# TouchPanelPrototype.net
KiCad netlist of a schematic drawn in EAGLE
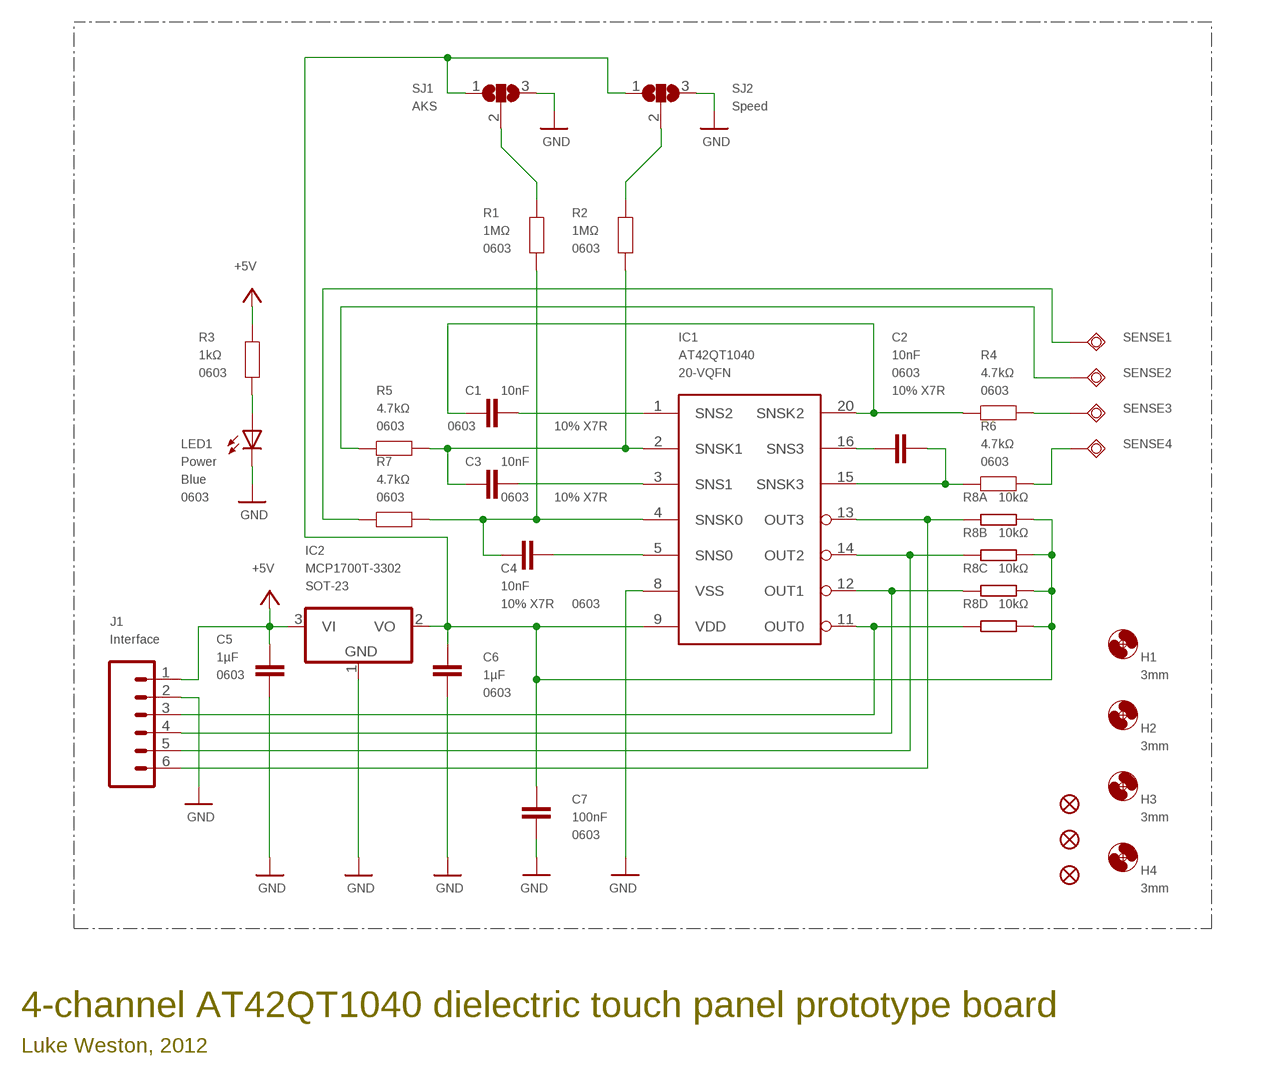
[diagram p0: schematic, sheet 1, part 1 of 2]
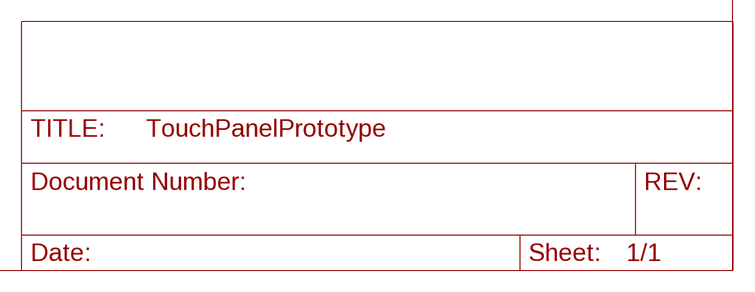
[diagram p1: schematic, sheet 1, part 2 of 2]

(export (version "E")
  (design (tool "Eeschema 10.0.6"))
  (components
    (comp (ref "C1")
      (value "10nF")
      (footprint "eagle-import:0603")
      (fields (field (name "INFO") "10% X7R") (field (name "PACKAGE") "0603"))
      (libsource (lib "eagle-import") (part "CAP0603"))
    )
    (comp (ref "C2")
      (value "10nF")
      (footprint "eagle-import:0603")
      (fields (field (name "INFO") "10% X7R") (field (name "PACKAGE") "0603"))
      (libsource (lib "eagle-import") (part "CAP0603"))
    )
    (comp (ref "C3")
      (value "10nF")
      (footprint "eagle-import:0603")
      (fields (field (name "INFO") "10% X7R") (field (name "PACKAGE") "0603"))
      (libsource (lib "eagle-import") (part "CAP0603"))
    )
    (comp (ref "C4")
      (value "10nF")
      (footprint "eagle-import:0603")
      (fields (field (name "INFO") "10% X7R") (field (name "PACKAGE") "0603"))
      (libsource (lib "eagle-import") (part "CAP0603"))
    )
    (comp (ref "C5")
      (value "1µF")
      (footprint "eagle-import:0603")
      (fields (field (name "PACKAGE") "0603"))
      (libsource (lib "eagle-import") (part "CAP0603"))
    )
    (comp (ref "C6")
      (value "1µF")
      (footprint "eagle-import:0603")
      (fields (field (name "PACKAGE") "0603"))
      (libsource (lib "eagle-import") (part "CAP0603"))
    )
    (comp (ref "C7")
      (value "100nF")
      (footprint "eagle-import:0603")
      (fields (field (name "PACKAGE") "0603"))
      (libsource (lib "eagle-import") (part "CAP0603"))
    )
    (comp (ref "H1")
      (value "3mm")
      (footprint "eagle-import:3,0")
      (libsource (lib "eagle-import") (part "MOUNT-HOLE3.0"))
    )
    (comp (ref "H2")
      (value "3mm")
      (footprint "eagle-import:3,0")
      (libsource (lib "eagle-import") (part "MOUNT-HOLE3.0"))
    )
    (comp (ref "H3")
      (value "3mm")
      (footprint "eagle-import:3,0")
      (libsource (lib "eagle-import") (part "MOUNT-HOLE3.0"))
    )
    (comp (ref "H4")
      (value "3mm")
      (footprint "eagle-import:3,0")
      (libsource (lib "eagle-import") (part "MOUNT-HOLE3.0"))
    )
    (comp (ref "IC1")
      (value "AT42QT1040")
      (footprint "eagle-import:QFN_MLF20")
      (fields (field (name "PACKAGE") "20-VQFN"))
      (libsource (lib "eagle-import") (part "AT42QT1040"))
    )
    (comp (ref "IC2")
      (value "MCP1700T-3302")
      (footprint "eagle-import:SOT23")
      (fields (field (name "PACKAGE") "SOT-23"))
      (libsource (lib "eagle-import") (part "MCP1703CB"))
    )
    (comp (ref "J1")
      (value "Interface")
      (footprint "eagle-import:1X06")
      (libsource (lib "eagle-import") (part "M06SIP"))
    )
    (comp (ref "JP1")
      (value "FIDUCIAL1X2")
      (footprint "eagle-import:FIDUCIAL-1X2")
      (libsource (lib "eagle-import") (part "FIDUCIAL1X2"))
    )
    (comp (ref "JP2")
      (value "FIDUCIAL1X2")
      (footprint "eagle-import:FIDUCIAL-1X2")
      (libsource (lib "eagle-import") (part "FIDUCIAL1X2"))
    )
    (comp (ref "JP3")
      (value "FIDUCIAL1X2")
      (footprint "eagle-import:FIDUCIAL-1X2")
      (libsource (lib "eagle-import") (part "FIDUCIAL1X2"))
    )
    (comp (ref "LED1")
      (value "Power")
      (footprint "eagle-import:LED-0603")
      (fields (field (name "COLOUR") "Blue") (field (name "PACKAGE") "0603"))
      (libsource (lib "eagle-import") (part "LED0603"))
    )
    (comp (ref "R1")
      (value "1MΩ")
      (footprint "eagle-import:0603")
      (fields (field (name "PACKAGE") "0603"))
      (libsource (lib "eagle-import") (part "RESISTOR0603"))
    )
    (comp (ref "R2")
      (value "1MΩ")
      (footprint "eagle-import:0603")
      (fields (field (name "PACKAGE") "0603"))
      (libsource (lib "eagle-import") (part "RESISTOR0603"))
    )
    (comp (ref "R3")
      (value "1kΩ")
      (footprint "eagle-import:0603")
      (fields (field (name "PACKAGE") "0603"))
      (libsource (lib "eagle-import") (part "RESISTOR0603"))
    )
    (comp (ref "R4")
      (value "4.7kΩ")
      (footprint "eagle-import:0603")
      (fields (field (name "PACKAGE") "0603"))
      (libsource (lib "eagle-import") (part "RESISTOR0603"))
    )
    (comp (ref "R5")
      (value "4.7kΩ")
      (footprint "eagle-import:0603")
      (fields (field (name "PACKAGE") "0603"))
      (libsource (lib "eagle-import") (part "RESISTOR0603"))
    )
    (comp (ref "R6")
      (value "4.7kΩ")
      (footprint "eagle-import:0603")
      (fields (field (name "PACKAGE") "0603"))
      (libsource (lib "eagle-import") (part "RESISTOR0603"))
    )
    (comp (ref "R7")
      (value "4.7kΩ")
      (footprint "eagle-import:0603")
      (fields (field (name "PACKAGE") "0603"))
      (libsource (lib "eagle-import") (part "RESISTOR0603"))
    )
    (comp (ref "R8")
      (value "10kΩ")
      (footprint "eagle-import:CAY16")
      (libsource (lib "eagle-import") (part "CAY16"))
    )
    (comp (ref "SENSE1")
      (value "TPSQTP20R")
      (footprint "eagle-import:TP20R")
      (libsource (lib "eagle-import") (part "TPSQTP20R"))
    )
    (comp (ref "SENSE2")
      (value "TPSQTP20R")
      (footprint "eagle-import:TP20R")
      (libsource (lib "eagle-import") (part "TPSQTP20R"))
    )
    (comp (ref "SENSE3")
      (value "TPSQTP20R")
      (footprint "eagle-import:TP20R")
      (libsource (lib "eagle-import") (part "TPSQTP20R"))
    )
    (comp (ref "SENSE4")
      (value "TPSQTP20R")
      (footprint "eagle-import:TP20R")
      (libsource (lib "eagle-import") (part "TPSQTP20R"))
    )
    (comp (ref "SJ1")
      (value "AKS")
      (footprint "eagle-import:SJ_2")
      (libsource (lib "eagle-import") (part "SJ2W"))
    )
    (comp (ref "SJ2")
      (value "Speed")
      (footprint "eagle-import:SJ_2")
      (libsource (lib "eagle-import") (part "SJ2W"))
    )
  )
  (nets
    (net (code "1") (name "+5V") (class "Default")
      (node (ref "C5") (pin "2") (pinfunction "2_2") (pintype "passive"))
      (node (ref "IC2") (pin "3") (pinfunction "VI_3") (pintype "input"))
      (node (ref "J1") (pin "1") (pinfunction "1_1") (pintype "passive"))
      (node (ref "R3") (pin "1") (pinfunction "1_1") (pintype "passive"))
    )
    (net (code "2") (name "GND") (class "Default")
      (node (ref "C5") (pin "1") (pinfunction "1_1") (pintype "passive"))
      (node (ref "C6") (pin "1") (pinfunction "1_1") (pintype "passive"))
      (node (ref "C7") (pin "1") (pinfunction "1_1") (pintype "passive"))
      (node (ref "IC1") (pin "8") (pinfunction "VSS_8") (pintype "power_in"))
      (node (ref "IC2") (pin "1") (pinfunction "GND_1") (pintype "passive"))
      (node (ref "J1") (pin "2") (pinfunction "2_2") (pintype "passive"))
      (node (ref "LED1") (pin "C") (pinfunction "C_C") (pintype "passive"))
      (node (ref "SJ1") (pin "3") (pinfunction "3_3") (pintype "passive"))
      (node (ref "SJ2") (pin "3") (pinfunction "3_3") (pintype "passive"))
    )
    (net (code "3") (name "Net-(IC1-OUT0)") (class "Default")
      (node (ref "IC1") (pin "11") (pinfunction "OUT0_11") (pintype "output"))
      (node (ref "J1") (pin "3") (pinfunction "3_3") (pintype "passive"))
      (node (ref "R8") (pin "5") (pinfunction "2_5") (pintype "passive"))
    )
    (net (code "4") (name "Net-(IC1-OUT1)") (class "Default")
      (node (ref "IC1") (pin "12") (pinfunction "OUT1_12") (pintype "output"))
      (node (ref "J1") (pin "4") (pinfunction "4_4") (pintype "passive"))
      (node (ref "R8") (pin "6") (pinfunction "2_6") (pintype "passive"))
    )
    (net (code "5") (name "Net-(IC1-OUT2)") (class "Default")
      (node (ref "IC1") (pin "14") (pinfunction "OUT2_14") (pintype "output"))
      (node (ref "J1") (pin "5") (pinfunction "5_5") (pintype "passive"))
      (node (ref "R8") (pin "7") (pinfunction "2_7") (pintype "passive"))
    )
    (net (code "6") (name "Net-(IC1-OUT3)") (class "Default")
      (node (ref "IC1") (pin "13") (pinfunction "OUT3_13") (pintype "output"))
      (node (ref "J1") (pin "6") (pinfunction "6_6") (pintype "passive"))
      (node (ref "R8") (pin "8") (pinfunction "2_8") (pintype "passive"))
    )
    (net (code "7") (name "Net-(IC1-SNS0)") (class "Default")
      (node (ref "C4") (pin "1") (pinfunction "1_1") (pintype "passive"))
      (node (ref "IC1") (pin "5") (pinfunction "SNS0_5") (pintype "bidirectional"))
    )
    (net (code "8") (name "Net-(IC1-SNS1)") (class "Default")
      (node (ref "C3") (pin "1") (pinfunction "1_1") (pintype "passive"))
      (node (ref "IC1") (pin "3") (pinfunction "SNS1_3") (pintype "bidirectional"))
    )
    (net (code "9") (name "Net-(IC1-SNS2)") (class "Default")
      (node (ref "C1") (pin "1") (pinfunction "1_1") (pintype "passive"))
      (node (ref "IC1") (pin "1") (pinfunction "SNS2_1") (pintype "bidirectional"))
    )
    (net (code "10") (name "Net-(IC1-SNS3)") (class "Default")
      (node (ref "C2") (pin "2") (pinfunction "2_2") (pintype "passive"))
      (node (ref "IC1") (pin "16") (pinfunction "SNS3_16") (pintype "bidirectional"))
    )
    (net (code "11") (name "Net-(IC1-SNSK0)") (class "Default")
      (node (ref "C4") (pin "2") (pinfunction "2_2") (pintype "passive"))
      (node (ref "IC1") (pin "4") (pinfunction "SNSK0_4") (pintype "bidirectional"))
      (node (ref "R1") (pin "2") (pinfunction "2_2") (pintype "passive"))
      (node (ref "R7") (pin "1") (pinfunction "1_1") (pintype "passive"))
    )
    (net (code "12") (name "Net-(IC1-SNSK1)") (class "Default")
      (node (ref "C3") (pin "2") (pinfunction "2_2") (pintype "passive"))
      (node (ref "IC1") (pin "2") (pinfunction "SNSK1_2") (pintype "bidirectional"))
      (node (ref "R2") (pin "2") (pinfunction "2_2") (pintype "passive"))
      (node (ref "R5") (pin "1") (pinfunction "1_1") (pintype "passive"))
    )
    (net (code "13") (name "Net-(IC1-SNSK2)") (class "Default")
      (node (ref "C1") (pin "2") (pinfunction "2_2") (pintype "passive"))
      (node (ref "IC1") (pin "20") (pinfunction "SNSK2_20") (pintype "bidirectional"))
      (node (ref "R4") (pin "2") (pinfunction "2_2") (pintype "passive"))
    )
    (net (code "14") (name "Net-(IC1-SNSK3)") (class "Default")
      (node (ref "C2") (pin "1") (pinfunction "1_1") (pintype "passive"))
      (node (ref "IC1") (pin "15") (pinfunction "SNSK3_15") (pintype "bidirectional"))
      (node (ref "R6") (pin "2") (pinfunction "2_2") (pintype "passive"))
    )
    (net (code "15") (name "Net-(IC1-VDD)") (class "Default")
      (node (ref "C6") (pin "2") (pinfunction "2_2") (pintype "passive"))
      (node (ref "C7") (pin "2") (pinfunction "2_2") (pintype "passive"))
      (node (ref "IC1") (pin "9") (pinfunction "VDD_9") (pintype "power_in"))
      (node (ref "IC2") (pin "2") (pinfunction "VO_2") (pintype "passive"))
      (node (ref "R8") (pin "1") (pinfunction "1_1") (pintype "passive"))
      (node (ref "R8") (pin "2") (pinfunction "1_2") (pintype "passive"))
      (node (ref "R8") (pin "3") (pinfunction "1_3") (pintype "passive"))
      (node (ref "R8") (pin "4") (pinfunction "1_4") (pintype "passive"))
      (node (ref "SJ1") (pin "1") (pinfunction "1_1") (pintype "passive"))
      (node (ref "SJ2") (pin "1") (pinfunction "1_1") (pintype "passive"))
    )
    (net (code "16") (name "Net-(LED1-PadA)") (class "Default")
      (node (ref "LED1") (pin "A") (pinfunction "A_A") (pintype "passive"))
      (node (ref "R3") (pin "2") (pinfunction "2_2") (pintype "passive"))
    )
    (net (code "17") (name "Net-(R1-Pad1)") (class "Default")
      (node (ref "R1") (pin "1") (pinfunction "1_1") (pintype "passive"))
      (node (ref "SJ1") (pin "2") (pinfunction "2_2") (pintype "passive"))
    )
    (net (code "18") (name "Net-(R2-Pad1)") (class "Default")
      (node (ref "R2") (pin "1") (pinfunction "1_1") (pintype "passive"))
      (node (ref "SJ2") (pin "2") (pinfunction "2_2") (pintype "passive"))
    )
    (net (code "19") (name "Net-(R4-Pad1)") (class "Default")
      (node (ref "R4") (pin "1") (pinfunction "1_1") (pintype "passive"))
      (node (ref "SENSE3") (pin "TP") (pinfunction "TP_TP") (pintype "input"))
    )
    (net (code "20") (name "Net-(R5-Pad2)") (class "Default")
      (node (ref "R5") (pin "2") (pinfunction "2_2") (pintype "passive"))
      (node (ref "SENSE2") (pin "TP") (pinfunction "TP_TP") (pintype "input"))
    )
    (net (code "21") (name "Net-(R6-Pad1)") (class "Default")
      (node (ref "R6") (pin "1") (pinfunction "1_1") (pintype "passive"))
      (node (ref "SENSE4") (pin "TP") (pinfunction "TP_TP") (pintype "input"))
    )
    (net (code "22") (name "Net-(R7-Pad2)") (class "Default")
      (node (ref "R7") (pin "2") (pinfunction "2_2") (pintype "passive"))
      (node (ref "SENSE1") (pin "TP") (pinfunction "TP_TP") (pintype "input"))
    )
  )
)
